# clock1_v1.net
KiCad netlist of a schematic drawn in EAGLE
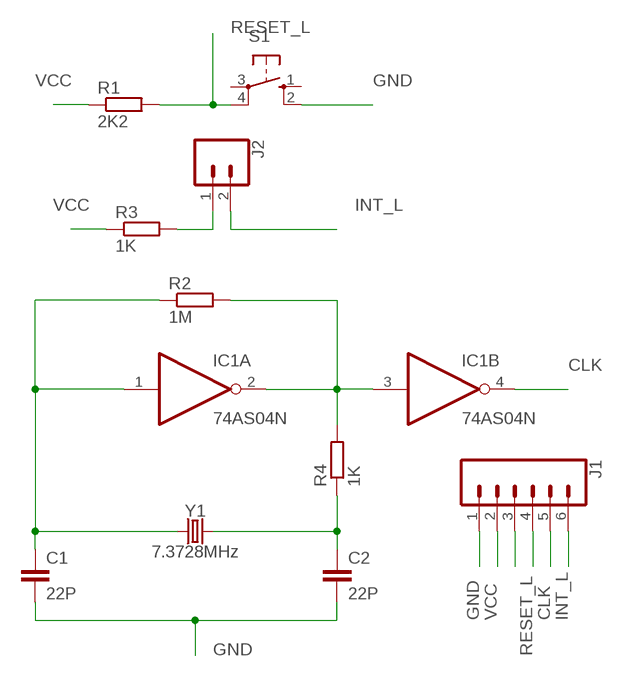
[diagram p0: schematic, sheet 1]

(export (version "E")
  (design (tool "Eeschema 10.0.6"))
  (components
    (comp (ref "C1")
      (value "22P")
      (footprint "eagle-import:C025-024X044")
      (libsource (lib "eagle-import") (part "C-EU025-024X044"))
    )
    (comp (ref "C2")
      (value "22P")
      (footprint "eagle-import:C025-024X044")
      (libsource (lib "eagle-import") (part "C-EU025-024X044"))
    )
    (comp (ref "IC1")
      (value "74AS04N")
      (footprint "eagle-import:DIL14")
      (libsource (lib "eagle-import") (part "7404NAS"))
    )
    (comp (ref "J1")
      (value "CONN_06LONGPADS")
      (footprint "eagle-import:1X06_LONGPADS")
      (libsource (lib "eagle-import") (part "CONN_06LONGPADS"))
    )
    (comp (ref "J2")
      (value "CONN_02PTH3")
      (footprint "eagle-import:1X02_LONGPADS")
      (libsource (lib "eagle-import") (part "CONN_02PTH3"))
    )
    (comp (ref "R1")
      (value "2K2")
      (footprint "eagle-import:0204_5")
      (libsource (lib "eagle-import") (part "R-EU_0204/5"))
    )
    (comp (ref "R2")
      (value "1M")
      (footprint "eagle-import:0204_5")
      (libsource (lib "eagle-import") (part "R-EU_0204/5"))
    )
    (comp (ref "R3")
      (value "1K")
      (footprint "eagle-import:0204_5")
      (libsource (lib "eagle-import") (part "R-EU_0204/5"))
    )
    (comp (ref "R4")
      (value "1K")
      (footprint "eagle-import:0204_5")
      (libsource (lib "eagle-import") (part "R-EU_0204/5"))
    )
    (comp (ref "S1")
      (value "10-XX")
      (footprint "eagle-import:B3F-10XX")
      (fields (field (name "MPN") "B3F-1000"))
      (libsource (lib "eagle-import") (part "10-XX"))
    )
    (comp (ref "Y1")
      (value "7.3728MHz")
      (footprint "eagle-import:HC49U")
      (libsource (lib "eagle-import") (part "CRYSTALPTH-HC49UV"))
    )
  )
  (nets
    (net (code "1") (name "/CLK") (class "Default")
      (node (ref "IC1") (pin "4") (pinfunction "O_4") (pintype "output"))
      (node (ref "J1") (pin "5") (pinfunction "5_5") (pintype "passive"))
    )
    (net (code "2") (name "/GND") (class "Default")
      (node (ref "C1") (pin "2") (pinfunction "2_2") (pintype "passive"))
      (node (ref "C2") (pin "2") (pinfunction "2_2") (pintype "passive"))
      (node (ref "J1") (pin "1") (pinfunction "1_1") (pintype "passive"))
      (node (ref "S1") (pin "2") (pinfunction "S1_2") (pintype "passive"))
    )
    (net (code "3") (name "/INT_L") (class "Default")
      (node (ref "J1") (pin "6") (pinfunction "6_6") (pintype "passive"))
      (node (ref "J2") (pin "2") (pinfunction "2_2") (pintype "passive"))
    )
    (net (code "4") (name "/RESET_L") (class "Default")
      (node (ref "J1") (pin "4") (pinfunction "4_4") (pintype "passive"))
      (node (ref "R1") (pin "2") (pinfunction "2_2") (pintype "passive"))
      (node (ref "S1") (pin "4") (pinfunction "P1_4") (pintype "passive"))
    )
    (net (code "5") (name "/VCC") (class "Default")
      (node (ref "J1") (pin "2") (pinfunction "2_2") (pintype "passive"))
      (node (ref "R1") (pin "1") (pinfunction "1_1") (pintype "passive"))
      (node (ref "R3") (pin "1") (pinfunction "1_1") (pintype "passive"))
    )
    (net (code "6") (name "Net-(C2-Pad1)") (class "Default")
      (node (ref "C2") (pin "1") (pinfunction "1_1") (pintype "passive"))
      (node (ref "R4") (pin "1") (pinfunction "1_1") (pintype "passive"))
      (node (ref "Y1") (pin "2") (pinfunction "2_2") (pintype "passive"))
    )
    (net (code "7") (name "Net-(IC1A-I)") (class "Default")
      (node (ref "C1") (pin "1") (pinfunction "1_1") (pintype "passive"))
      (node (ref "IC1") (pin "1") (pinfunction "I_1") (pintype "input"))
      (node (ref "R2") (pin "1") (pinfunction "1_1") (pintype "passive"))
      (node (ref "Y1") (pin "1") (pinfunction "1_1") (pintype "passive"))
    )
    (net (code "8") (name "Net-(IC1A-O)") (class "Default")
      (node (ref "IC1") (pin "2") (pinfunction "O_2") (pintype "output"))
      (node (ref "IC1") (pin "3") (pinfunction "I_3") (pintype "input"))
      (node (ref "R2") (pin "2") (pinfunction "2_2") (pintype "passive"))
      (node (ref "R4") (pin "2") (pinfunction "2_2") (pintype "passive"))
    )
    (net (code "9") (name "Net-(J2-Pad1)") (class "Default")
      (node (ref "J2") (pin "1") (pinfunction "1_1") (pintype "passive"))
      (node (ref "R3") (pin "2") (pinfunction "2_2") (pintype "passive"))
    )
    (net (code "10") (name "unconnected-(J1-Pad3)") (class "Default")
      (node (ref "J1") (pin "3") (pinfunction "3_3") (pintype "passive"))
    )
    (net (code "11") (name "unconnected-(S1-P-Pad3)") (class "Default")
      (node (ref "S1") (pin "3") (pinfunction "P_3") (pintype "passive"))
    )
    (net (code "12") (name "unconnected-(S1-S-Pad1)") (class "Default")
      (node (ref "S1") (pin "1") (pinfunction "S_1") (pintype "passive"))
    )
  )
)
